# 004-H-01_SD_data_logger.net
KiCad netlist of a schematic drawn in Altium Designer
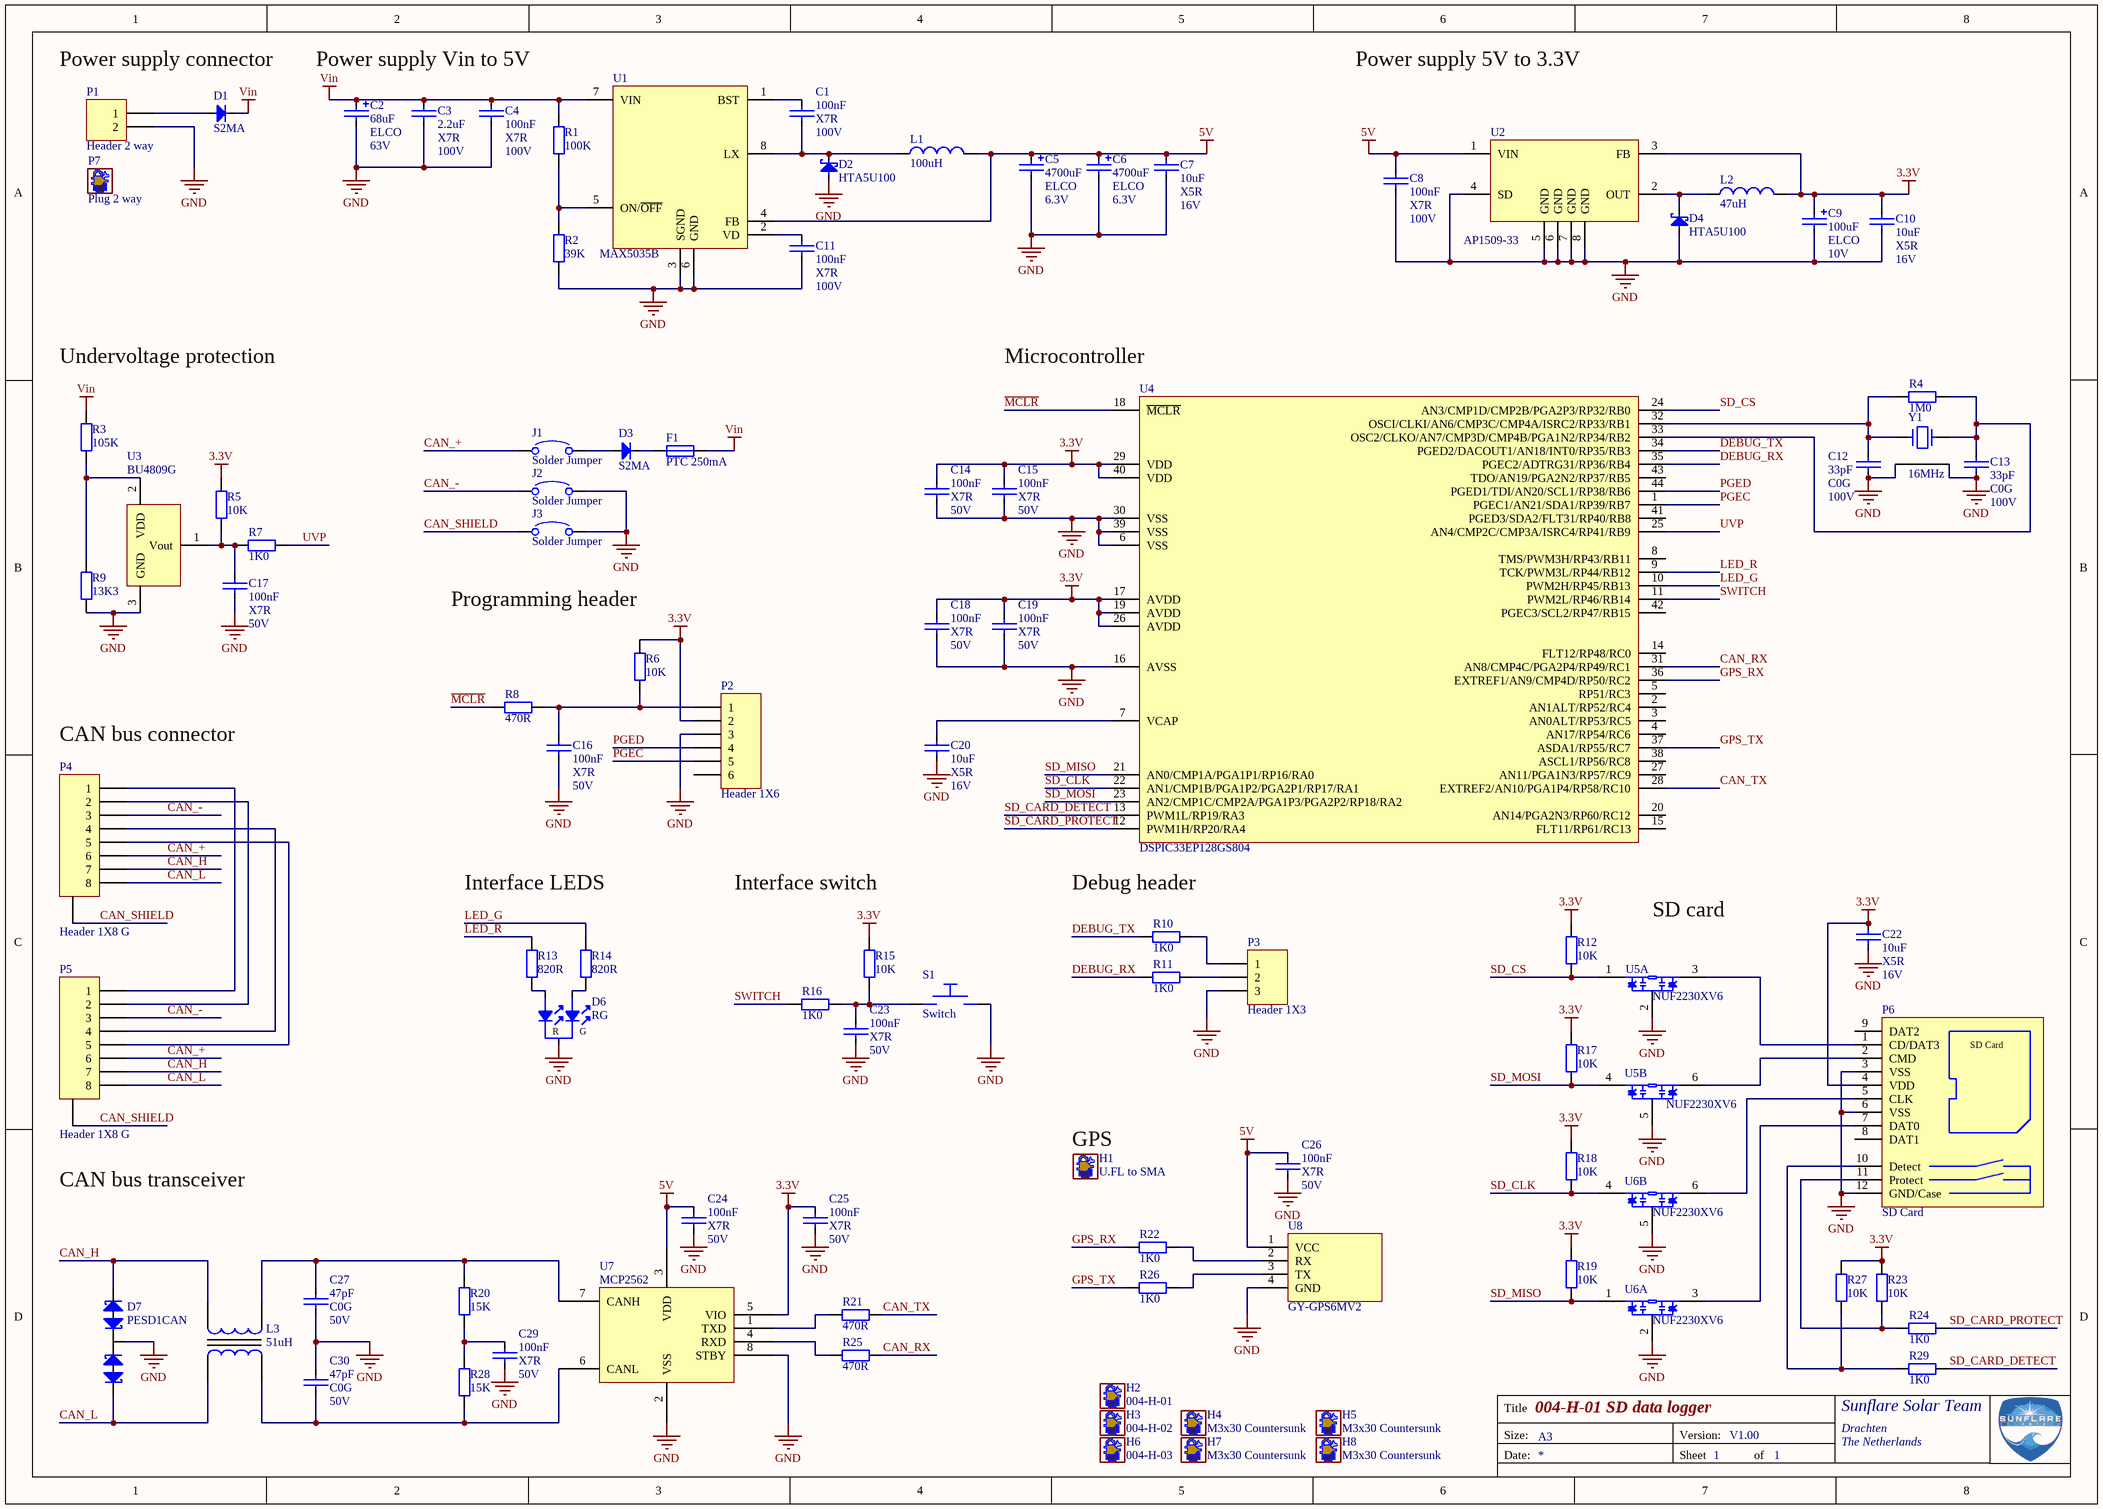
[diagram p0: 004-H-01 SD data logger.SchDoc]

(export (version "E")
  (design (tool "Eeschema 10.0.6"))
  (components
    (comp (ref "C1")
      (value "100nF")
      (footprint "CAP0805")
      (description "Capacitor")
      (fields (field (name "DIELECTRIC") "X7R") (field (name "VOLTAGERATING") "100V"))
      (libsource (lib "004-H-01 SD data logger") (part "Capacitor"))
    )
    (comp (ref "C2")
      (value "68uF")
      (footprint "CAPP8383X62N")
      (description "Capacitor Pol")
      (fields
        (field (name "MANUFACTURER") "Panasonic")
        (field (name "MANUFACTURER PART NO") "EEEFK1J680UP")
        (field (name "DIELECTRIC") "ELCO")
        (field (name "VOLTAGERATING") "63V")
      )
      (libsource (lib "004-H-01 SD data logger") (part "CapacitorPol"))
    )
    (comp (ref "C3")
      (value "2.2uF")
      (footprint "CAP1210")
      (description "Capacitor")
      (fields
        (field (name "MANUFACTURER") "AVX")
        (field (name "MANUFACTURER PART NO") "C1210X225K1RACTU")
        (field (name "DIELECTRIC") "X7R")
        (field (name "VOLTAGERATING") "100V")
      )
      (libsource (lib "004-H-01 SD data logger") (part "Capacitor"))
    )
    (comp (ref "C4")
      (value "100nF")
      (footprint "CAP0805")
      (description "Capacitor")
      (fields (field (name "DIELECTRIC") "X7R") (field (name "VOLTAGERATING") "100V"))
      (libsource (lib "004-H-01 SD data logger") (part "Capacitor"))
    )
    (comp (ref "C5")
      (value "4700uF")
      (footprint "CAPPOL_leaded_D12_5L20P5")
      (description "Capacitor Pol")
      (fields
        (field (name "MANUFACTURER") "Panasonic")
        (field (name "MANUFACTURER PART NO") "ECA0JM472")
        (field (name "DIELECTRIC") "ELCO")
        (field (name "VOLTAGERATING") "6.3V")
      )
      (libsource (lib "004-H-01 SD data logger") (part "CapacitorPol"))
    )
    (comp (ref "C6")
      (value "4700uF")
      (footprint "CAPPOL_leaded_D12_5L20P5")
      (description "Capacitor Pol")
      (fields
        (field (name "MANUFACTURER") "Panasonic")
        (field (name "MANUFACTURER PART NO") "ECA0JM472")
        (field (name "DIELECTRIC") "ELCO")
        (field (name "VOLTAGERATING") "6.3V")
      )
      (libsource (lib "004-H-01 SD data logger") (part "CapacitorPol"))
    )
    (comp (ref "C7")
      (value "10uF")
      (footprint "CAP1210")
      (description "Capacitor")
      (fields
        (field (name "MANUFACTURER") "Multicomp")
        (field (name "MANUFACTURER PART NO") "MC1210X106K160CT")
        (field (name "DIELECTRIC") "X5R")
        (field (name "VOLTAGERATING") "16V")
      )
      (libsource (lib "004-H-01 SD data logger") (part "Capacitor"))
    )
    (comp (ref "C8")
      (value "100nF")
      (footprint "CAP0805")
      (description "Capacitor")
      (fields (field (name "DIELECTRIC") "X7R") (field (name "VOLTAGERATING") "100V"))
      (libsource (lib "004-H-01 SD data logger") (part "Capacitor"))
    )
    (comp (ref "C9")
      (value "100uF")
      (footprint "CAPP8383X62N")
      (description "Capacitor Pol")
      (fields
        (field (name "MANUFACTURER") "Panasonic")
        (field (name "MANUFACTURER PART NO") "EEEHA1A101P")
        (field (name "DIELECTRIC") "ELCO")
        (field (name "VOLTAGERATING") "10V")
      )
      (libsource (lib "004-H-01 SD data logger") (part "CapacitorPol"))
    )
    (comp (ref "C10")
      (value "10uF")
      (footprint "CAP1210")
      (description "Capacitor")
      (fields
        (field (name "MANUFACTURER") "Multicomp")
        (field (name "MANUFACTURER PART NO") "MC1210X106K160CT")
        (field (name "DIELECTRIC") "X5R")
        (field (name "VOLTAGERATING") "16V")
      )
      (libsource (lib "004-H-01 SD data logger") (part "Capacitor"))
    )
    (comp (ref "C11")
      (value "100nF")
      (footprint "CAP0805")
      (description "Capacitor")
      (fields (field (name "DIELECTRIC") "X7R") (field (name "VOLTAGERATING") "100V"))
      (libsource (lib "004-H-01 SD data logger") (part "Capacitor"))
    )
    (comp (ref "C12")
      (value "33pF")
      (footprint "CAP0603")
      (description "Capacitor")
      (fields (field (name "DIELECTRIC") "C0G") (field (name "VOLTAGERATING") "100V"))
      (libsource (lib "004-H-01 SD data logger") (part "Capacitor"))
    )
    (comp (ref "C13")
      (value "33pF")
      (footprint "CAP0603")
      (description "Capacitor")
      (fields (field (name "DIELECTRIC") "C0G") (field (name "VOLTAGERATING") "100V"))
      (libsource (lib "004-H-01 SD data logger") (part "Capacitor"))
    )
    (comp (ref "C14")
      (value "100nF")
      (footprint "CAP0603")
      (description "Capacitor")
      (fields (field (name "DIELECTRIC") "X7R") (field (name "VOLTAGERATING") "50V"))
      (libsource (lib "004-H-01 SD data logger") (part "Capacitor"))
    )
    (comp (ref "C15")
      (value "100nF")
      (footprint "CAP0603")
      (description "Capacitor")
      (fields (field (name "DIELECTRIC") "X7R") (field (name "VOLTAGERATING") "50V"))
      (libsource (lib "004-H-01 SD data logger") (part "Capacitor"))
    )
    (comp (ref "C16")
      (value "100nF")
      (footprint "CAP0603")
      (description "Capacitor")
      (fields (field (name "DIELECTRIC") "X7R") (field (name "VOLTAGERATING") "50V"))
      (libsource (lib "004-H-01 SD data logger") (part "Capacitor"))
    )
    (comp (ref "C17")
      (value "100nF")
      (footprint "CAP0603")
      (description "Capacitor")
      (fields (field (name "DIELECTRIC") "X7R") (field (name "VOLTAGERATING") "50V"))
      (libsource (lib "004-H-01 SD data logger") (part "Capacitor"))
    )
    (comp (ref "C18")
      (value "100nF")
      (footprint "CAP0603")
      (description "Capacitor")
      (fields (field (name "DIELECTRIC") "X7R") (field (name "VOLTAGERATING") "50V"))
      (libsource (lib "004-H-01 SD data logger") (part "Capacitor"))
    )
    (comp (ref "C19")
      (value "100nF")
      (footprint "CAP0603")
      (description "Capacitor")
      (fields (field (name "DIELECTRIC") "X7R") (field (name "VOLTAGERATING") "50V"))
      (libsource (lib "004-H-01 SD data logger") (part "Capacitor"))
    )
    (comp (ref "C20")
      (value "10uF")
      (footprint "CAP1210")
      (description "Capacitor")
      (fields
        (field (name "MANUFACTURER") "Multicomp")
        (field (name "MANUFACTURER PART NO") "MC1210X106K160CT")
        (field (name "DIELECTRIC") "X5R")
        (field (name "VOLTAGERATING") "16V")
      )
      (libsource (lib "004-H-01 SD data logger") (part "Capacitor"))
    )
    (comp (ref "C22")
      (value "10uF")
      (footprint "CAP1210")
      (description "Capacitor")
      (fields
        (field (name "MANUFACTURER") "Multicomp")
        (field (name "MANUFACTURER PART NO") "MC1210X106K160CT")
        (field (name "DIELECTRIC") "X5R")
        (field (name "VOLTAGERATING") "16V")
      )
      (libsource (lib "004-H-01 SD data logger") (part "Capacitor"))
    )
    (comp (ref "C23")
      (value "100nF")
      (footprint "CAP0603")
      (description "Capacitor")
      (fields (field (name "DIELECTRIC") "X7R") (field (name "VOLTAGERATING") "50V"))
      (libsource (lib "004-H-01 SD data logger") (part "Capacitor"))
    )
    (comp (ref "C24")
      (value "100nF")
      (footprint "CAP0603")
      (description "Capacitor")
      (fields (field (name "DIELECTRIC") "X7R") (field (name "VOLTAGERATING") "50V"))
      (libsource (lib "004-H-01 SD data logger") (part "Capacitor"))
    )
    (comp (ref "C25")
      (value "100nF")
      (footprint "CAP0603")
      (description "Capacitor")
      (fields (field (name "DIELECTRIC") "X7R") (field (name "VOLTAGERATING") "50V"))
      (libsource (lib "004-H-01 SD data logger") (part "Capacitor"))
    )
    (comp (ref "C26")
      (value "100nF")
      (footprint "CAP0603")
      (description "Capacitor")
      (fields (field (name "DIELECTRIC") "X7R") (field (name "VOLTAGERATING") "50V"))
      (libsource (lib "004-H-01 SD data logger") (part "Capacitor"))
    )
    (comp (ref "C27")
      (value "47pF")
      (footprint "CAP0603")
      (description "Capacitor")
      (fields (field (name "DIELECTRIC") "C0G") (field (name "VOLTAGERATING") "50V"))
      (libsource (lib "004-H-01 SD data logger") (part "Capacitor"))
    )
    (comp (ref "C29")
      (value "100nF")
      (footprint "CAP0603")
      (description "Capacitor")
      (fields (field (name "DIELECTRIC") "X7R") (field (name "VOLTAGERATING") "50V"))
      (libsource (lib "004-H-01 SD data logger") (part "Capacitor"))
    )
    (comp (ref "C30")
      (value "47pF")
      (footprint "CAP0603")
      (description "Capacitor")
      (fields (field (name "DIELECTRIC") "C0G") (field (name "VOLTAGERATING") "50V"))
      (libsource (lib "004-H-01 SD data logger") (part "Capacitor"))
    )
    (comp (ref "D1")
      (value "S2MA")
      (footprint "DIODEDO-214AC")
      (description "Diode")
      (fields (field (name "MANUFACTURER") "Multicomp"))
      (libsource (lib "004-H-01 SD data logger") (part "Diode"))
    )
    (comp (ref "D2")
      (value "HTA5U100")
      (footprint "DIODEDO-214AC")
      (description "Diode Schottky")
      (fields (field (name "MANUFACTURER") "Multicomp"))
      (libsource (lib "004-H-01 SD data logger") (part "Diode Schottky"))
    )
    (comp (ref "D3")
      (value "S2MA")
      (footprint "DIODEDO-214AC")
      (description "Diode")
      (fields (field (name "MANUFACTURER") "Multicomp"))
      (libsource (lib "004-H-01 SD data logger") (part "Diode"))
    )
    (comp (ref "D4")
      (value "HTA5U100")
      (footprint "DIODEDO-214AC")
      (description "Diode Schottky")
      (fields (field (name "MANUFACTURER") "Multicomp"))
      (libsource (lib "004-H-01 SD data logger") (part "Diode Schottky"))
    )
    (comp (ref "D6")
      (value "RG")
      (footprint "LED_RG_COMMON_GND")
      (description "Led RG")
      (fields (field (name "MANUFACTURER") "Multicomp") (field (name "MANUFACTURER PART NO") "MCL039PURGW"))
      (libsource (lib "004-H-01 SD data logger") (part "Led_RG_Common_GND"))
    )
    (comp (ref "D7")
      (value "PESD1CAN")
      (footprint "SOT23-3N")
      (description "ESD Protection Device, TVS, 70 V, SOT-23, 3 Pins")
      (fields (field (name "MANUFACTURER") "NXP"))
      (libsource (lib "004-H-01 SD data logger") (part "PESD1CAN"))
    )
    (comp (ref "F1")
      (value "PTC 250mA")
      (footprint "Fuse1210")
      (description "Fuse")
      (fields (field (name "MANUFACTURER") "Bel Fuse") (field (name "MANUFACTURER PART NO") "0ZCH0010FF2E"))
      (libsource (lib "004-H-01 SD data logger") (part "Fuse"))
    )
    (comp (ref "H1")
      (value "U.FL to SMA")
      (description "RF / Coaxial Cable Assembly, U.FL Jack to SMA Bulkhead Jack, 50 ohm, 0.25 ft, 75 mm")
      (fields
        (field (name "MANUFACTURER") "RF SOLUTIONS")
        (field (name "MANUFACTURER PART NO") "CBA-UFLSMA-1")
      )
      (libsource (lib "004-H-01 SD data logger") (part "Hardware"))
    )
    (comp (ref "H2")
      (value "004-H-01")
      (description "PCB")
      (libsource (lib "004-H-01 SD data logger") (part "Hardware"))
    )
    (comp (ref "H3")
      (value "004-H-02")
      (description "Casing bottom")
      (libsource (lib "004-H-01 SD data logger") (part "Hardware"))
    )
    (comp (ref "H4")
      (value "M3x30 Countersunk")
      (description "M3x30 Xountersunk Bolt")
      (libsource (lib "004-H-01 SD data logger") (part "Hardware"))
    )
    (comp (ref "H5")
      (value "M3x30 Countersunk")
      (description "M3x30 Xountersunk Bolt")
      (libsource (lib "004-H-01 SD data logger") (part "Hardware"))
    )
    (comp (ref "H6")
      (value "004-H-03")
      (description "Casing top")
      (libsource (lib "004-H-01 SD data logger") (part "Hardware"))
    )
    (comp (ref "H7")
      (value "M3x30 Countersunk")
      (description "M3x30 Xountersunk Bolt")
      (libsource (lib "004-H-01 SD data logger") (part "Hardware"))
    )
    (comp (ref "H8")
      (value "M3x30 Countersunk")
      (description "M3x30 Xountersunk Bolt")
      (libsource (lib "004-H-01 SD data logger") (part "Hardware"))
    )
    (comp (ref "J1")
      (value "Solder Jumper")
      (footprint "SolderJumer")
      (description "Solder jumper open")
      (libsource (lib "004-H-01 SD data logger") (part "SolderJumper"))
    )
    (comp (ref "J2")
      (value "Solder Jumper")
      (footprint "SolderJumer")
      (description "Solder jumper open")
      (libsource (lib "004-H-01 SD data logger") (part "SolderJumper"))
    )
    (comp (ref "J3")
      (value "Solder Jumper")
      (footprint "SolderJumer")
      (description "Solder jumper open")
      (libsource (lib "004-H-01 SD data logger") (part "SolderJumper"))
    )
    (comp (ref "L1")
      (value "100uH")
      (footprint "INDP3030X28N")
      (description "Inductor")
      (fields (field (name "MANUFACTURER") "BOURNS") (field (name "MANUFACTURER PART NO") "SDR0302-101KL"))
      (libsource (lib "004-H-01 SD data logger") (part "Inductor"))
    )
    (comp (ref "L2")
      (value "47uH")
      (footprint "INDP3030X28N")
      (description "Inductor")
      (fields (field (name "MANUFACTURER") "Bourns") (field (name "MANUFACTURER PART NO") "SDR0302-470KL"))
      (libsource (lib "004-H-01 SD data logger") (part "Inductor"))
    )
    (comp (ref "L3")
      (value "51uH")
      (footprint "IND200P450X300-4N")
      (description "Choke common mode")
      (fields (field (name "MANUFACTURER") "Bourns") (field (name "MANUFACTURER PART NO") "SRF4532-510Y"))
      (libsource (lib "004-H-01 SD data logger") (part "Choke Common Mode"))
    )
    (comp (ref "P1")
      (value "Header 2 way")
      (footprint "21.95MH/2-E")
      (fields
        (field (name "MANUFACTURER") "IMO PRECISION CONTROLS")
        (field (name "MANUFACTURER PART NO") "21.95MH/2-E")
      )
      (libsource (lib "004-H-01 SD data logger") (part "Header1X2"))
    )
    (comp (ref "P2")
      (value "Header 1X6")
      (footprint "Header1X6P100")
      (description "Connector 1X6")
      (fields (field (name "MANUFACTURER") "Multicomp") (field (name "MANUFACTURER PART NO") "2211S-06G"))
      (libsource (lib "004-H-01 SD data logger") (part "Header1X6"))
    )
    (comp (ref "P3")
      (value "Header 1X3")
      (footprint "Header1X3P100")
      (description "Connector 1X3")
      (fields (field (name "MANUFACTURER") "Multicomp") (field (name "MANUFACTURER PART NO") "2211S-03G"))
      (libsource (lib "004-H-01 SD data logger") (part "Header1X3"))
    )
    (comp (ref "P4")
      (value "Header 1X8 G")
      (footprint "TECO-1-406541-5")
      (description "Connector 1X8 with Ground")
      (fields
        (field (name "MANUFACTURER") "TE CONNECTIVITY")
        (field (name "MANUFACTURER PART NO") "1-406541-5")
      )
      (libsource (lib "004-H-01 SD data logger") (part "Header1X8+G"))
    )
    (comp (ref "P5")
      (value "Header 1X8 G")
      (footprint "TECO-1-406541-5")
      (description "Connector 1X8 with Ground")
      (fields
        (field (name "MANUFACTURER") "TE CONNECTIVITY")
        (field (name "MANUFACTURER PART NO") "1-406541-5")
      )
      (libsource (lib "004-H-01 SD data logger") (part "Header1X8+G"))
    )
    (comp (ref "P6")
      (value "SD Card")
      (footprint "SDK-9BNS-K13-GS-TB")
      (description "SD slot connector with card detect and protect")
      (fields (field (name "MANUFACTURER") "JST") (field (name "MANUFACTURER PART NO") "SDK-9BNS-K13-GS-TB"))
      (libsource (lib "004-H-01 SD data logger") (part "SD slot"))
    )
    (comp (ref "P7")
      (value "Plug 2 way")
      (description "Generaric hardware")
      (fields
        (field (name "MANUFACTURER") "IMO PRECISION CONTROLS")
        (field (name "MANUFACTURER PART NO") "21.950M/2-E")
      )
      (libsource (lib "004-H-01 SD data logger") (part "Hardware"))
    )
    (comp (ref "R1")
      (value "100K")
      (footprint "RES0805")
      (description "Resistor")
      (fields (field (name "TOLERANCE") "1%"))
      (libsource (lib "") (part "Resistor_1"))
    )
    (comp (ref "R2")
      (value "39K")
      (footprint "RES0805")
      (description "Resistor")
      (fields (field (name "TOLERANCE") "1%"))
      (libsource (lib "") (part "Resistor_1"))
    )
    (comp (ref "R3")
      (value "105K")
      (footprint "RES0805")
      (description "Resistor")
      (fields (field (name "TOLERANCE") "1%"))
      (libsource (lib "") (part "Resistor_1"))
    )
    (comp (ref "R4")
      (value "1M0")
      (footprint "RES0603")
      (description "Resistor")
      (fields (field (name "TOLERANCE") "1%"))
      (libsource (lib "004-H-01 SD data logger") (part "Resistor"))
    )
    (comp (ref "R5")
      (value "10K")
      (footprint "RES0603")
      (description "Resistor")
      (fields (field (name "TOLERANCE") "1%"))
      (libsource (lib "") (part "Resistor_1"))
    )
    (comp (ref "R6")
      (value "10K")
      (footprint "RES0603")
      (description "Resistor")
      (fields (field (name "TOLERANCE") "1%"))
      (libsource (lib "") (part "Resistor_1"))
    )
    (comp (ref "R7")
      (value "1K0")
      (footprint "RES0603")
      (description "Resistor")
      (fields (field (name "TOLERANCE") "1%"))
      (libsource (lib "004-H-01 SD data logger") (part "Resistor"))
    )
    (comp (ref "R8")
      (value "470R")
      (footprint "RES0603")
      (description "Resistor")
      (fields (field (name "TOLERANCE") "1%"))
      (libsource (lib "004-H-01 SD data logger") (part "Resistor"))
    )
    (comp (ref "R9")
      (value "13K3")
      (footprint "RES0805")
      (description "Resistor")
      (fields (field (name "TOLERANCE") "1%"))
      (libsource (lib "") (part "Resistor_1"))
    )
    (comp (ref "R10")
      (value "1K0")
      (footprint "RES0603")
      (description "Resistor")
      (fields (field (name "TOLERANCE") "1%"))
      (libsource (lib "004-H-01 SD data logger") (part "Resistor"))
    )
    (comp (ref "R11")
      (value "1K0")
      (footprint "RES0603")
      (description "Resistor")
      (fields (field (name "TOLERANCE") "1%"))
      (libsource (lib "004-H-01 SD data logger") (part "Resistor"))
    )
    (comp (ref "R12")
      (value "10K")
      (footprint "RES0603")
      (description "Resistor")
      (fields (field (name "TOLERANCE") "1%"))
      (libsource (lib "") (part "Resistor_1"))
    )
    (comp (ref "R13")
      (value "820R")
      (footprint "RES0603")
      (description "Resistor")
      (fields (field (name "TOLERANCE") "1%"))
      (libsource (lib "") (part "Resistor_1"))
    )
    (comp (ref "R14")
      (value "820R")
      (footprint "RES0603")
      (description "Resistor")
      (fields (field (name "TOLERANCE") "1%"))
      (libsource (lib "") (part "Resistor_1"))
    )
    (comp (ref "R15")
      (value "10K")
      (footprint "RES0603")
      (description "Resistor")
      (fields (field (name "TOLERANCE") "1%"))
      (libsource (lib "") (part "Resistor_1"))
    )
    (comp (ref "R16")
      (value "1K0")
      (footprint "RES0603")
      (description "Resistor")
      (fields (field (name "TOLERANCE") "1%"))
      (libsource (lib "004-H-01 SD data logger") (part "Resistor"))
    )
    (comp (ref "R17")
      (value "10K")
      (footprint "RES0603")
      (description "Resistor")
      (fields (field (name "TOLERANCE") "1%"))
      (libsource (lib "") (part "Resistor_1"))
    )
    (comp (ref "R18")
      (value "10K")
      (footprint "RES0603")
      (description "Resistor")
      (fields (field (name "TOLERANCE") "1%"))
      (libsource (lib "") (part "Resistor_1"))
    )
    (comp (ref "R19")
      (value "10K")
      (footprint "RES0603")
      (description "Resistor")
      (fields (field (name "TOLERANCE") "1%"))
      (libsource (lib "") (part "Resistor_1"))
    )
    (comp (ref "R20")
      (value "15K")
      (footprint "RES0603")
      (description "Resistor")
      (fields (field (name "TOLERANCE") "1%"))
      (libsource (lib "") (part "Resistor_1"))
    )
    (comp (ref "R21")
      (value "470R")
      (footprint "RES0603")
      (description "Resistor")
      (fields (field (name "TOLERANCE") "1%"))
      (libsource (lib "004-H-01 SD data logger") (part "Resistor"))
    )
    (comp (ref "R22")
      (value "1K0")
      (footprint "RES0603")
      (description "Resistor")
      (fields (field (name "TOLERANCE") "1%"))
      (libsource (lib "004-H-01 SD data logger") (part "Resistor"))
    )
    (comp (ref "R23")
      (value "10K")
      (footprint "RES0603")
      (description "Resistor")
      (fields (field (name "TOLERANCE") "1%"))
      (libsource (lib "") (part "Resistor_1"))
    )
    (comp (ref "R24")
      (value "1K0")
      (footprint "RES0603")
      (description "Resistor")
      (fields (field (name "TOLERANCE") "1%"))
      (libsource (lib "004-H-01 SD data logger") (part "Resistor"))
    )
    (comp (ref "R25")
      (value "470R")
      (footprint "RES0603")
      (description "Resistor")
      (fields (field (name "TOLERANCE") "1%"))
      (libsource (lib "004-H-01 SD data logger") (part "Resistor"))
    )
    (comp (ref "R26")
      (value "1K0")
      (footprint "RES0603")
      (description "Resistor")
      (fields (field (name "TOLERANCE") "1%"))
      (libsource (lib "004-H-01 SD data logger") (part "Resistor"))
    )
    (comp (ref "R27")
      (value "10K")
      (footprint "RES0603")
      (description "Resistor")
      (fields (field (name "TOLERANCE") "1%"))
      (libsource (lib "") (part "Resistor_1"))
    )
    (comp (ref "R28")
      (value "15K")
      (footprint "RES0603")
      (description "Resistor")
      (fields (field (name "TOLERANCE") "1%"))
      (libsource (lib "") (part "Resistor_1"))
    )
    (comp (ref "R29")
      (value "1K0")
      (footprint "RES0603")
      (description "Resistor")
      (fields (field (name "TOLERANCE") "1%"))
      (libsource (lib "004-H-01 SD data logger") (part "Resistor"))
    )
    (comp (ref "S1")
      (value "Switch")
      (footprint "FSMRA4JH")
      (description "Tactile Switch")
      (fields
        (field (name "MANUFACTURER") "TE CONNECTIVITY")
        (field (name "MANUFACTURER PART NO") "FSMRA4JH")
      )
      (libsource (lib "004-H-01 SD data logger") (part "TactileSwitch"))
    )
    (comp (ref "U1")
      (value "MAX5035B")
      (footprint "SOIC-8N")
      (description "5V 1A, 76V, High-Efficiency MAXPower Step-Down DC-DC Converter")
      (fields
        (field (name "MANUFACTURER") "Maxim Integrated Products")
        (field (name "MANUFACTURER PART NO") "MAX5035BUSA+T")
      )
      (libsource (lib "004-H-01 SD data logger") (part "MAX5035B"))
    )
    (comp (ref "U2")
      (value "AP1509-33")
      (footprint "SOIC-8N")
      (description "150KHz, 2A PWM BUCK DC/DC CONVERTER")
      (fields
        (field (name "MANUFACTURER") "Diodes Inc")
        (field (name "MANUFACTURER PART NO") "AP1509-33SG-13")
      )
      (libsource (lib "004-H-01 SD data logger") (part "AP1509-33"))
    )
    (comp (ref "U3")
      (value "BU4809G")
      (footprint "SOT95P280X125-5N")
      (description "Voltage Detector")
      (fields (field (name "MANUFACTURER") "ROHM") (field (name "MANUFACTURER PART NO") "BU4809G-TR"))
      (libsource (lib "004-H-01 SD data logger") (part "BD48xx"))
    )
    (comp (ref "U4")
      (value "DSPIC33EP128GS804")
      (footprint "TQFP80P1200X1200X120-44N")
      (fields
        (field (name "MANUFACTURER") "Microchip")
        (field (name "MANUFACTURER PART NO") "DSPIC33EP128GS804-I/PT")
      )
      (libsource (lib "004-H-01 SD data logger") (part "DSPIC33EP128GS804"))
    )
    (comp (ref "U5")
      (value "NUF2230XV6")
      (footprint "SOT50P160X60-6N")
      (description "2 Line EMI Filter with ESDProtection")
      (fields
        (field (name "MANUFACTURER") "ON SEMICONDUCTOR")
        (field (name "MANUFACTURER PART NO") "NUF2230XV6T1G")
      )
      (libsource (lib "004-H-01 SD data logger") (part "NUF2230XV6"))
    )
    (comp (ref "U6")
      (value "NUF2230XV6")
      (footprint "SOT50P160X60-6N")
      (description "2 Line EMI Filter with ESDProtection")
      (fields
        (field (name "MANUFACTURER") "ON SEMICONDUCTOR")
        (field (name "MANUFACTURER PART NO") "NUF2230XV6T1G")
      )
      (libsource (lib "004-H-01 SD data logger") (part "NUF2230XV6"))
    )
    (comp (ref "U7")
      (value "MCP2562")
      (footprint "SOIC-8N")
      (description "CAN Bus, Transceiver, CAN, LIN, 1, 1, 4.5 V, 5.5 V, SOIC")
      (fields (field (name "MANUFACTURER") "Microchip") (field (name "MANUFACTURER PART NO") "MCP2562-E/SN"))
      (libsource (lib "004-H-01 SD data logger") (part "MCP2562"))
    )
    (comp (ref "U8")
      (value "GY-GPS6MV2")
      (footprint "GY-GPS6MV2")
      (description "GPS module")
      (fields (field (name "MANUFACTURER") "Ebay") (field (name "MANUFACTURER PART NO") "GY-NEO6MV2"))
      (libsource (lib "004-H-01 SD data logger") (part "GY-GPS6MV2"))
    )
    (comp (ref "Y1")
      (value "16MHz")
      (footprint "CrystalSMD 5032")
      (description "Crystal")
      (fields
        (field (name "MANUFACTURER") "MULTICOMP")
        (field (name "MANUFACTURER PART NO") "MCSJK-7I-16.00-18-30-60-B-30")
      )
      (libsource (lib "004-H-01 SD data logger") (part "Crystal_1"))
    )
  )
  (nets
    (net (code "1") (name "/CAN_+") (class "Default")
      (node (ref "J1") (pin "1") (pinfunction "1_1") (pintype "passive"))
      (node (ref "P4") (pin "6") (pinfunction "6_6") (pintype "passive"))
      (node (ref "P5") (pin "6") (pinfunction "6_6") (pintype "passive"))
    )
    (net (code "2") (name "/CAN_-") (class "Default")
      (node (ref "J2") (pin "1") (pinfunction "1_1") (pintype "passive"))
      (node (ref "P4") (pin "3") (pinfunction "3_3") (pintype "passive"))
      (node (ref "P5") (pin "3") (pinfunction "3_3") (pintype "passive"))
    )
    (net (code "3") (name "/CAN_H") (class "Default")
      (node (ref "D7") (pin "1") (pinfunction "1_1") (pintype "passive"))
      (node (ref "L3") (pin "4") (pinfunction "4_4") (pintype "passive"))
      (node (ref "P4") (pin "7") (pinfunction "7_7") (pintype "passive"))
      (node (ref "P5") (pin "7") (pinfunction "7_7") (pintype "passive"))
    )
    (net (code "4") (name "/CAN_L") (class "Default")
      (node (ref "D7") (pin "2") (pinfunction "2_2") (pintype "passive"))
      (node (ref "L3") (pin "1") (pinfunction "1_1") (pintype "passive"))
      (node (ref "P4") (pin "8") (pinfunction "8_8") (pintype "passive"))
      (node (ref "P5") (pin "8") (pinfunction "8_8") (pintype "passive"))
    )
    (net (code "5") (name "/CAN_RX") (class "Default")
      (node (ref "R25") (pin "2") (pinfunction "2_2") (pintype "passive"))
      (node (ref "U4") (pin "31") (pinfunction "AN8/CMP4C/PGA2P4/RP49/RC1_31") (pintype "passive"))
    )
    (net (code "6") (name "/CAN_SHIELD") (class "Default")
      (node (ref "J3") (pin "1") (pinfunction "1_1") (pintype "passive"))
      (node (ref "P4") (pin "9") (pinfunction "G_9") (pintype "passive"))
      (node (ref "P5") (pin "9") (pinfunction "G_9") (pintype "passive"))
    )
    (net (code "7") (name "/CAN_TX") (class "Default")
      (node (ref "R21") (pin "2") (pinfunction "2_2") (pintype "passive"))
      (node (ref "U4") (pin "28") (pinfunction "EXTREF2/AN10/PGA1P4/RP58/RC10_28") (pintype "passive"))
    )
    (net (code "8") (name "/DEBUG_RX") (class "Default")
      (node (ref "R11") (pin "1") (pinfunction "1_1") (pintype "passive"))
      (node (ref "U4") (pin "35") (pinfunction "PGEC2/ADTRG31/RP36/RB4_35") (pintype "passive"))
    )
    (net (code "9") (name "/DEBUG_TX") (class "Default")
      (node (ref "R10") (pin "1") (pinfunction "1_1") (pintype "passive"))
      (node (ref "U4") (pin "34") (pinfunction "PGED2/DACOUT1/AN18/INT0/RP35/RB3_34") (pintype "passive"))
    )
    (net (code "10") (name "/GPS_RX") (class "Default")
      (node (ref "R22") (pin "1") (pinfunction "1_1") (pintype "passive"))
      (node (ref "U4") (pin "36") (pinfunction "EXTREF1/AN9/CMP4D/RP50/RC2_36") (pintype "passive"))
    )
    (net (code "11") (name "/GPS_TX") (class "Default")
      (node (ref "R26") (pin "1") (pinfunction "1_1") (pintype "passive"))
      (node (ref "U4") (pin "37") (pinfunction "ASDA1/RP55/RC7_37") (pintype "passive"))
    )
    (net (code "12") (name "/LED_G") (class "Default")
      (node (ref "R14") (pin "1") (pinfunction "1_1") (pintype "passive"))
      (node (ref "U4") (pin "10") (pinfunction "PWM2H/RP45/RB13_10") (pintype "passive"))
    )
    (net (code "13") (name "/LED_R") (class "Default")
      (node (ref "R13") (pin "1") (pinfunction "1_1") (pintype "passive"))
      (node (ref "U4") (pin "9") (pinfunction "TCK/PWM3L/RP44/RB12_9") (pintype "passive"))
    )
    (net (code "14") (name "/PGEC") (class "Default")
      (node (ref "P2") (pin "5") (pinfunction "5_5") (pintype "passive"))
      (node (ref "U4") (pin "1") (pinfunction "PGEC1/AN21/SDA1/RP39/RB7_1") (pintype "passive"))
    )
    (net (code "15") (name "/PGED") (class "Default")
      (node (ref "P2") (pin "4") (pinfunction "4_4") (pintype "passive"))
      (node (ref "U4") (pin "44") (pinfunction "PGED1/TDI/AN20/SCL1/RP38/RB6_44") (pintype "passive"))
    )
    (net (code "16") (name "/SD_CARD_DETECT") (class "Default")
      (node (ref "R29") (pin "2") (pinfunction "2_2") (pintype "passive"))
      (node (ref "U4") (pin "13") (pinfunction "PWM1L/RP19/RA3_13") (pintype "passive"))
    )
    (net (code "17") (name "/SD_CARD_PROTECT") (class "Default")
      (node (ref "R24") (pin "2") (pinfunction "2_2") (pintype "passive"))
      (node (ref "U4") (pin "12") (pinfunction "PWM1H/RP20/RA4_12") (pintype "passive"))
    )
    (net (code "18") (name "/SD_CLK") (class "Default")
      (node (ref "R18") (pin "2") (pinfunction "2_2") (pintype "passive"))
      (node (ref "U4") (pin "22") (pinfunction "AN1/CMP1B/PGA1P2/PGA2P1/RP17/RA1_22") (pintype "passive"))
      (node (ref "U6") (pin "4") (pinfunction "4_4") (pintype "passive"))
    )
    (net (code "19") (name "/SD_CS") (class "Default")
      (node (ref "R12") (pin "2") (pinfunction "2_2") (pintype "passive"))
      (node (ref "U4") (pin "24") (pinfunction "AN3/CMP1D/CMP2B/PGA2P3/RP32/RB0_24") (pintype "passive"))
      (node (ref "U5") (pin "1") (pinfunction "1_1") (pintype "passive"))
    )
    (net (code "20") (name "/SD_MISO") (class "Default")
      (node (ref "R19") (pin "2") (pinfunction "2_2") (pintype "passive"))
      (node (ref "U4") (pin "21") (pinfunction "AN0/CMP1A/PGA1P1/RP16/RA0_21") (pintype "passive"))
      (node (ref "U6") (pin "1") (pinfunction "1_1") (pintype "passive"))
    )
    (net (code "21") (name "/SD_MOSI") (class "Default")
      (node (ref "R17") (pin "2") (pinfunction "2_2") (pintype "passive"))
      (node (ref "U4") (pin "23") (pinfunction "AN2/CMP1C/CMP2A/PGA1P3/PGA2P2/RP18/RA2_23") (pintype "passive"))
      (node (ref "U5") (pin "4") (pinfunction "4_4") (pintype "passive"))
    )
    (net (code "22") (name "/SWITCH") (class "Default")
      (node (ref "R16") (pin "1") (pinfunction "1_1") (pintype "passive"))
      (node (ref "U4") (pin "11") (pinfunction "PWM2L/RP46/RB14_11") (pintype "passive"))
    )
    (net (code "23") (name "/UVP") (class "Default")
      (node (ref "R7") (pin "2") (pinfunction "2_2") (pintype "passive"))
      (node (ref "U4") (pin "25") (pinfunction "AN4/CMP2C/CMP3A/ISRC4/RP41/RB9_25") (pintype "passive"))
    )
    (net (code "24") (name "/~{MCLR}") (class "Default")
      (node (ref "R8") (pin "1") (pinfunction "1_1") (pintype "passive"))
      (node (ref "U4") (pin "18") (pinfunction "~{MCLR}_18") (pintype "passive"))
    )
    (net (code "25") (name "3.3V") (class "Default")
      (node (ref "C10") (pin "2") (pinfunction "2_2") (pintype "passive"))
      (node (ref "C14") (pin "2") (pinfunction "2_2") (pintype "passive"))
      (node (ref "C15") (pin "2") (pinfunction "2_2") (pintype "passive"))
      (node (ref "C18") (pin "2") (pinfunction "2_2") (pintype "passive"))
      (node (ref "C19") (pin "2") (pinfunction "2_2") (pintype "passive"))
      (node (ref "C22") (pin "2") (pinfunction "2_2") (pintype "passive"))
      (node (ref "C25") (pin "2") (pinfunction "2_2") (pintype "passive"))
      (node (ref "C9") (pin "1") (pinfunction "1_1") (pintype "passive"))
      (node (ref "L2") (pin "2") (pinfunction "2_2") (pintype "passive"))
      (node (ref "P2") (pin "2") (pinfunction "2_2") (pintype "passive"))
      (node (ref "P6") (pin "4") (pinfunction "VDD_4") (pintype "passive"))
      (node (ref "R12") (pin "1") (pinfunction "1_1") (pintype "passive"))
      (node (ref "R15") (pin "1") (pinfunction "1_1") (pintype "passive"))
      (node (ref "R17") (pin "1") (pinfunction "1_1") (pintype "passive"))
      (node (ref "R18") (pin "1") (pinfunction "1_1") (pintype "passive"))
      (node (ref "R19") (pin "1") (pinfunction "1_1") (pintype "passive"))
      (node (ref "R23") (pin "1") (pinfunction "1_1") (pintype "passive"))
      (node (ref "R27") (pin "1") (pinfunction "1_1") (pintype "passive"))
      (node (ref "R5") (pin "1") (pinfunction "1_1") (pintype "passive"))
      (node (ref "R6") (pin "1") (pinfunction "1_1") (pintype "passive"))
      (node (ref "U2") (pin "3") (pinfunction "FB_3") (pintype "passive"))
      (node (ref "U4") (pin "17") (pinfunction "AVDD_17") (pintype "passive"))
      (node (ref "U4") (pin "19") (pinfunction "AVDD_19") (pintype "passive"))
      (node (ref "U4") (pin "26") (pinfunction "AVDD_26") (pintype "passive"))
      (node (ref "U4") (pin "29") (pinfunction "VDD_29") (pintype "passive"))
      (node (ref "U4") (pin "40") (pinfunction "VDD_40") (pintype "passive"))
      (node (ref "U7") (pin "5") (pinfunction "VIO_5") (pintype "passive"))
    )
    (net (code "26") (name "5V") (class "Default")
      (node (ref "C24") (pin "2") (pinfunction "2_2") (pintype "passive"))
      (node (ref "C26") (pin "2") (pinfunction "2_2") (pintype "passive"))
      (node (ref "C5") (pin "1") (pinfunction "1_1") (pintype "passive"))
      (node (ref "C6") (pin "1") (pinfunction "1_1") (pintype "passive"))
      (node (ref "C7") (pin "2") (pinfunction "2_2") (pintype "passive"))
      (node (ref "C8") (pin "2") (pinfunction "2_2") (pintype "passive"))
      (node (ref "L1") (pin "2") (pinfunction "2_2") (pintype "passive"))
      (node (ref "U1") (pin "4") (pinfunction "FB_4") (pintype "passive"))
      (node (ref "U2") (pin "1") (pinfunction "VIN_1") (pintype "passive"))
      (node (ref "U7") (pin "3") (pinfunction "VDD_3") (pintype "passive"))
      (node (ref "U8") (pin "1") (pinfunction "VCC_1") (pintype "passive"))
    )
    (net (code "27") (name "GND") (class "Default")
      (node (ref "C10") (pin "1") (pinfunction "1_1") (pintype "passive"))
      (node (ref "C11") (pin "1") (pinfunction "1_1") (pintype "passive"))
      (node (ref "C12") (pin "1") (pinfunction "1_1") (pintype "passive"))
      (node (ref "C13") (pin "1") (pinfunction "1_1") (pintype "passive"))
      (node (ref "C14") (pin "1") (pinfunction "1_1") (pintype "passive"))
      (node (ref "C15") (pin "1") (pinfunction "1_1") (pintype "passive"))
      (node (ref "C16") (pin "2") (pinfunction "2_2") (pintype "passive"))
      (node (ref "C17") (pin "2") (pinfunction "2_2") (pintype "passive"))
      (node (ref "C18") (pin "1") (pinfunction "1_1") (pintype "passive"))
      (node (ref "C19") (pin "1") (pinfunction "1_1") (pintype "passive"))
      (node (ref "C2") (pin "2") (pinfunction "2_2") (pintype "passive"))
      (node (ref "C20") (pin "1") (pinfunction "1_1") (pintype "passive"))
      (node (ref "C22") (pin "1") (pinfunction "1_1") (pintype "passive"))
      (node (ref "C23") (pin "1") (pinfunction "1_1") (pintype "passive"))
      (node (ref "C24") (pin "1") (pinfunction "1_1") (pintype "passive"))
      (node (ref "C25") (pin "1") (pinfunction "1_1") (pintype "passive"))
      (node (ref "C26") (pin "1") (pinfunction "1_1") (pintype "passive"))
      (node (ref "C27") (pin "1") (pinfunction "1_1") (pintype "passive"))
      (node (ref "C29") (pin "1") (pinfunction "1_1") (pintype "passive"))
      (node (ref "C3") (pin "1") (pinfunction "1_1") (pintype "passive"))
      (node (ref "C30") (pin "2") (pinfunction "2_2") (pintype "passive"))
      (node (ref "C4") (pin "1") (pinfunction "1_1") (pintype "passive"))
      (node (ref "C5") (pin "2") (pinfunction "2_2") (pintype "passive"))
      (node (ref "C6") (pin "2") (pinfunction "2_2") (pintype "passive"))
      (node (ref "C7") (pin "1") (pinfunction "1_1") (pintype "passive"))
      (node (ref "C8") (pin "1") (pinfunction "1_1") (pintype "passive"))
      (node (ref "C9") (pin "2") (pinfunction "2_2") (pintype "passive"))
      (node (ref "D2") (pin "2") (pinfunction "A_2") (pintype "passive"))
      (node (ref "D4") (pin "2") (pinfunction "A_2") (pintype "passive"))
      (node (ref "D6") (pin "2") (pinfunction "K_2") (pintype "passive"))
      (node (ref "D7") (pin "3") (pinfunction "3_3") (pintype "passive"))
      (node (ref "J2") (pin "2") (pinfunction "2_2") (pintype "passive"))
      (node (ref "J3") (pin "2") (pinfunction "2_2") (pintype "passive"))
      (node (ref "P1") (pin "2") (pinfunction "2_2") (pintype "passive"))
      (node (ref "P2") (pin "3") (pinfunction "3_3") (pintype "passive"))
      (node (ref "P3") (pin "3") (pinfunction "3_3") (pintype "passive"))
      (node (ref "P6") (pin "12") (pinfunction "GND/Case_12") (pintype "passive"))
      (node (ref "P6") (pin "3") (pinfunction "VSS_3") (pintype "passive"))
      (node (ref "P6") (pin "6") (pinfunction "VSS_6") (pintype "passive"))
      (node (ref "R2") (pin "2") (pinfunction "2_2") (pintype "passive"))
      (node (ref "R9") (pin "2") (pinfunction "2_2") (pintype "passive"))
      (node (ref "S1") (pin "2") (pinfunction "2_2") (pintype "passive"))
      (node (ref "U1") (pin "3") (pinfunction "SGND_3") (pintype "passive"))
      (node (ref "U1") (pin "6") (pinfunction "GND_6") (pintype "passive"))
      (node (ref "U2") (pin "4") (pinfunction "SD_4") (pintype "passive"))
      (node (ref "U2") (pin "5") (pinfunction "GND_5") (pintype "passive"))
      (node (ref "U2") (pin "6") (pinfunction "GND_6") (pintype "passive"))
      (node (ref "U2") (pin "7") (pinfunction "GND_7") (pintype "passive"))
      (node (ref "U2") (pin "8") (pinfunction "GND_8") (pintype "passive"))
      (node (ref "U3") (pin "3") (pinfunction "GND_3") (pintype "passive"))
      (node (ref "U4") (pin "16") (pinfunction "AVSS_16") (pintype "passive"))
      (node (ref "U4") (pin "30") (pinfunction "VSS_30") (pintype "passive"))
      (node (ref "U4") (pin "39") (pinfunction "VSS_39") (pintype "passive"))
      (node (ref "U4") (pin "6") (pinfunction "VSS_6") (pintype "passive"))
      (node (ref "U5") (pin "2") (pinfunction "2_2") (pintype "passive"))
      (node (ref "U5") (pin "5") (pinfunction "5_5") (pintype "passive"))
      (node (ref "U6") (pin "2") (pinfunction "2_2") (pintype "passive"))
      (node (ref "U6") (pin "5") (pinfunction "5_5") (pintype "passive"))
      (node (ref "U7") (pin "2") (pinfunction "VSS_2") (pintype "passive"))
      (node (ref "U7") (pin "8") (pinfunction "STBY_8") (pintype "passive"))
      (node (ref "U8") (pin "4") (pinfunction "GND_4") (pintype "passive"))
      (node (ref "Y1") (pin "2") (pinfunction "2_2") (pintype "passive"))
      (node (ref "Y1") (pin "4") (pinfunction "4_4") (pintype "passive"))
    )
    (net (code "28") (name "Net-(C16-Pad1)") (class "Default")
      (node (ref "C16") (pin "1") (pinfunction "1_1") (pintype "passive"))
      (node (ref "P2") (pin "1") (pinfunction "1_1") (pintype "passive"))
      (node (ref "R6") (pin "2") (pinfunction "2_2") (pintype "passive"))
      (node (ref "R8") (pin "2") (pinfunction "2_2") (pintype "passive"))
    )
    (net (code "29") (name "Net-(C23-Pad2)") (class "Default")
      (node (ref "C23") (pin "2") (pinfunction "2_2") (pintype "passive"))
      (node (ref "R15") (pin "2") (pinfunction "2_2") (pintype "passive"))
      (node (ref "R16") (pin "2") (pinfunction "2_2") (pintype "passive"))
      (node (ref "S1") (pin "1") (pinfunction "1_1") (pintype "passive"))
    )
    (net (code "30") (name "Net-(C29-Pad2)") (class "Default")
      (node (ref "C29") (pin "2") (pinfunction "2_2") (pintype "passive"))
      (node (ref "R20") (pin "2") (pinfunction "2_2") (pintype "passive"))
      (node (ref "R28") (pin "1") (pinfunction "1_1") (pintype "passive"))
    )
    (net (code "31") (name "Net-(D1-A)") (class "Default")
      (node (ref "D1") (pin "2") (pinfunction "A_2") (pintype "passive"))
      (node (ref "P1") (pin "1") (pinfunction "1_1") (pintype "passive"))
    )
    (net (code "32") (name "Net-(D2-K)") (class "Default")
      (node (ref "C1") (pin "1") (pinfunction "1_1") (pintype "passive"))
      (node (ref "D2") (pin "1") (pinfunction "K_1") (pintype "passive"))
      (node (ref "L1") (pin "1") (pinfunction "1_1") (pintype "passive"))
      (node (ref "U1") (pin "8") (pinfunction "LX_8") (pintype "passive"))
    )
    (net (code "33") (name "Net-(D3-A)") (class "Default")
      (node (ref "D3") (pin "2") (pinfunction "A_2") (pintype "passive"))
      (node (ref "J1") (pin "2") (pinfunction "2_2") (pintype "passive"))
    )
    (net (code "34") (name "Net-(D3-K)") (class "Default")
      (node (ref "D3") (pin "1") (pinfunction "K_1") (pintype "passive"))
      (node (ref "F1") (pin "1") (pinfunction "1_1") (pintype "passive"))
    )
    (net (code "35") (name "Net-(D4-K)") (class "Default")
      (node (ref "D4") (pin "1") (pinfunction "K_1") (pintype "passive"))
      (node (ref "L2") (pin "1") (pinfunction "1_1") (pintype "passive"))
      (node (ref "U2") (pin "2") (pinfunction "OUT_2") (pintype "passive"))
    )
    (net (code "36") (name "Net-(D6-A_G)") (class "Default")
      (node (ref "D6") (pin "3") (pinfunction "A_G_3") (pintype "passive"))
      (node (ref "R14") (pin "2") (pinfunction "2_2") (pintype "passive"))
    )
    (net (code "37") (name "Net-(D6-A_R)") (class "Default")
      (node (ref "D6") (pin "1") (pinfunction "A_R_1") (pintype "passive"))
      (node (ref "R13") (pin "2") (pinfunction "2_2") (pintype "passive"))
    )
    (net (code "38") (name "Net-(P3-Pad1)") (class "Default")
      (node (ref "P3") (pin "1") (pinfunction "1_1") (pintype "passive"))
      (node (ref "R10") (pin "2") (pinfunction "2_2") (pintype "passive"))
    )
    (net (code "39") (name "Net-(P3-Pad2)") (class "Default")
      (node (ref "P3") (pin "2") (pinfunction "2_2") (pintype "passive"))
      (node (ref "R11") (pin "2") (pinfunction "2_2") (pintype "passive"))
    )
    (net (code "40") (name "Net-(P4-Pad1)") (class "Default")
      (node (ref "P4") (pin "1") (pinfunction "1_1") (pintype "passive"))
      (node (ref "P5") (pin "1") (pinfunction "1_1") (pintype "passive"))
    )
    (net (code "41") (name "Net-(P4-Pad2)") (class "Default")
      (node (ref "P4") (pin "2") (pinfunction "2_2") (pintype "passive"))
      (node (ref "P5") (pin "2") (pinfunction "2_2") (pintype "passive"))
    )
    (net (code "42") (name "Net-(P4-Pad4)") (class "Default")
      (node (ref "P4") (pin "4") (pinfunction "4_4") (pintype "passive"))
      (node (ref "P5") (pin "4") (pinfunction "4_4") (pintype "passive"))
    )
    (net (code "43") (name "Net-(P4-Pad5)") (class "Default")
      (node (ref "P4") (pin "5") (pinfunction "5_5") (pintype "passive"))
      (node (ref "P5") (pin "5") (pinfunction "5_5") (pintype "passive"))
    )
    (net (code "44") (name "Net-(P6-CD{slash}DAT3)") (class "Default")
      (node (ref "P6") (pin "1") (pinfunction "CD/DAT3_1") (pintype "passive"))
      (node (ref "U5") (pin "3") (pinfunction "3_3") (pintype "passive"))
    )
    (net (code "45") (name "Net-(P6-CLK)") (class "Default")
      (node (ref "P6") (pin "5") (pinfunction "CLK_5") (pintype "passive"))
      (node (ref "U6") (pin "6") (pinfunction "6_6") (pintype "passive"))
    )
    (net (code "46") (name "Net-(P6-CMD)") (class "Default")
      (node (ref "P6") (pin "2") (pinfunction "CMD_2") (pintype "passive"))
      (node (ref "U5") (pin "6") (pinfunction "6_6") (pintype "passive"))
    )
    (net (code "47") (name "Net-(P6-DAT0)") (class "Default")
      (node (ref "P6") (pin "7") (pinfunction "DAT0_7") (pintype "passive"))
      (node (ref "U6") (pin "3") (pinfunction "3_3") (pintype "passive"))
    )
    (net (code "48") (name "Net-(P6-Detect)") (class "Default")
      (node (ref "P6") (pin "10") (pinfunction "Detect_10") (pintype "passive"))
      (node (ref "R27") (pin "2") (pinfunction "2_2") (pintype "passive"))
      (node (ref "R29") (pin "1") (pinfunction "1_1") (pintype "passive"))
    )
    (net (code "49") (name "Net-(P6-Protect)") (class "Default")
      (node (ref "P6") (pin "11") (pinfunction "Protect_11") (pintype "passive"))
      (node (ref "R23") (pin "2") (pinfunction "2_2") (pintype "passive"))
      (node (ref "R24") (pin "1") (pinfunction "1_1") (pintype "passive"))
    )
    (net (code "50") (name "Net-(U1-BST)") (class "Default")
      (node (ref "C1") (pin "2") (pinfunction "2_2") (pintype "passive"))
      (node (ref "U1") (pin "1") (pinfunction "BST_1") (pintype "passive"))
    )
    (net (code "51") (name "Net-(U1-ON{slash}~{OFF})") (class "Default")
      (node (ref "R1") (pin "2") (pinfunction "2_2") (pintype "passive"))
      (node (ref "R2") (pin "1") (pinfunction "1_1") (pintype "passive"))
      (node (ref "U1") (pin "5") (pinfunction "ON/~{OFF}_5") (pintype "passive"))
    )
    (net (code "52") (name "Net-(U1-VD)") (class "Default")
      (node (ref "C11") (pin "2") (pinfunction "2_2") (pintype "passive"))
      (node (ref "U1") (pin "2") (pinfunction "VD_2") (pintype "passive"))
    )
    (net (code "53") (name "Net-(U3-VDD)") (class "Default")
      (node (ref "R3") (pin "2") (pinfunction "2_2") (pintype "passive"))
      (node (ref "R9") (pin "1") (pinfunction "1_1") (pintype "passive"))
      (node (ref "U3") (pin "2") (pinfunction "VDD_2") (pintype "passive"))
    )
    (net (code "54") (name "Net-(U3-Vout)") (class "Default")
      (node (ref "C17") (pin "1") (pinfunction "1_1") (pintype "passive"))
      (node (ref "R5") (pin "2") (pinfunction "2_2") (pintype "passive"))
      (node (ref "R7") (pin "1") (pinfunction "1_1") (pintype "passive"))
      (node (ref "U3") (pin "1") (pinfunction "Vout_1") (pintype "passive"))
    )
    (net (code "55") (name "Net-(U4-OSC2{slash}CLKO{slash}AN7{slash}CMP3D{slash}CMP4B{slash}PGA1N2{slash}RP34{slash}RB2)") (class "Default")
      (node (ref "C13") (pin "2") (pinfunction "2_2") (pintype "passive"))
      (node (ref "R4") (pin "2") (pinfunction "2_2") (pintype "passive"))
      (node (ref "U4") (pin "33") (pinfunction "OSC2/CLKO/AN7/CMP3D/CMP4B/PGA1N2/RP34/RB2_33") (pintype "passive"))
      (node (ref "Y1") (pin "3") (pinfunction "3_3") (pintype "passive"))
    )
    (net (code "56") (name "Net-(U4-OSCI{slash}CLKI{slash}AN6{slash}CMP3C{slash}CMP4A{slash}ISRC2{slash}RP33{slash}RB1)") (class "Default")
      (node (ref "C12") (pin "2") (pinfunction "2_2") (pintype "passive"))
      (node (ref "R4") (pin "1") (pinfunction "1_1") (pintype "passive"))
      (node (ref "U4") (pin "32") (pinfunction "OSCI/CLKI/AN6/CMP3C/CMP4A/ISRC2/RP33/RB1_32") (pintype "passive"))
      (node (ref "Y1") (pin "1") (pinfunction "1_1") (pintype "passive"))
    )
    (net (code "57") (name "Net-(U4-VCAP)") (class "Default")
      (node (ref "C20") (pin "2") (pinfunction "2_2") (pintype "passive"))
      (node (ref "U4") (pin "7") (pinfunction "VCAP_7") (pintype "passive"))
    )
    (net (code "58") (name "Net-(U7-CANH)") (class "Default")
      (node (ref "C27") (pin "2") (pinfunction "2_2") (pintype "passive"))
      (node (ref "L3") (pin "3") (pinfunction "3_3") (pintype "passive"))
      (node (ref "R20") (pin "1") (pinfunction "1_1") (pintype "passive"))
      (node (ref "U7") (pin "7") (pinfunction "CANH_7") (pintype "passive"))
    )
    (net (code "59") (name "Net-(U7-CANL)") (class "Default")
      (node (ref "C30") (pin "1") (pinfunction "1_1") (pintype "passive"))
      (node (ref "L3") (pin "2") (pinfunction "2_2") (pintype "passive"))
      (node (ref "R28") (pin "2") (pinfunction "2_2") (pintype "passive"))
      (node (ref "U7") (pin "6") (pinfunction "CANL_6") (pintype "passive"))
    )
    (net (code "60") (name "Net-(U7-RXD)") (class "Default")
      (node (ref "R25") (pin "1") (pinfunction "1_1") (pintype "passive"))
      (node (ref "U7") (pin "4") (pinfunction "RXD_4") (pintype "passive"))
    )
    (net (code "61") (name "Net-(U7-TXD)") (class "Default")
      (node (ref "R21") (pin "1") (pinfunction "1_1") (pintype "passive"))
      (node (ref "U7") (pin "1") (pinfunction "TXD_1") (pintype "passive"))
    )
    (net (code "62") (name "Net-(U8-RX)") (class "Default")
      (node (ref "R22") (pin "2") (pinfunction "2_2") (pintype "passive"))
      (node (ref "U8") (pin "2") (pinfunction "RX_2") (pintype "passive"))
    )
    (net (code "63") (name "Net-(U8-TX)") (class "Default")
      (node (ref "R26") (pin "2") (pinfunction "2_2") (pintype "passive"))
      (node (ref "U8") (pin "3") (pinfunction "TX_3") (pintype "passive"))
    )
    (net (code "64") (name "Vin") (class "Default")
      (node (ref "C2") (pin "1") (pinfunction "1_1") (pintype "passive"))
      (node (ref "C3") (pin "2") (pinfunction "2_2") (pintype "passive"))
      (node (ref "C4") (pin "2") (pinfunction "2_2") (pintype "passive"))
      (node (ref "D1") (pin "1") (pinfunction "K_1") (pintype "passive"))
      (node (ref "F1") (pin "2") (pinfunction "2_2") (pintype "passive"))
      (node (ref "R1") (pin "1") (pinfunction "1_1") (pintype "passive"))
      (node (ref "R3") (pin "1") (pinfunction "1_1") (pintype "passive"))
      (node (ref "U1") (pin "7") (pinfunction "VIN_7") (pintype "passive"))
    )
    (net (code "65") (name "unconnected-(P2-Pad6)") (class "Default")
      (node (ref "P2") (pin "6") (pinfunction "6_6") (pintype "passive"))
    )
    (net (code "66") (name "unconnected-(P6-DAT1-Pad8)") (class "Default")
      (node (ref "P6") (pin "8") (pinfunction "DAT1_8") (pintype "passive"))
    )
    (net (code "67") (name "unconnected-(P6-DAT2-Pad9)") (class "Default")
      (node (ref "P6") (pin "9") (pinfunction "DAT2_9") (pintype "passive"))
    )
    (net (code "68") (name "unconnected-(U4-AN0ALT{slash}RP53{slash}RC5-Pad3)") (class "Default")
      (node (ref "U4") (pin "3") (pinfunction "AN0ALT/RP53/RC5_3") (pintype "passive"))
    )
    (net (code "69") (name "unconnected-(U4-AN1ALT{slash}RP52{slash}RC4-Pad2)") (class "Default")
      (node (ref "U4") (pin "2") (pinfunction "AN1ALT/RP52/RC4_2") (pintype "passive"))
    )
    (net (code "70") (name "unconnected-(U4-AN11{slash}PGA1N3{slash}RP57{slash}RC9-Pad27)") (class "Default")
      (node (ref "U4") (pin "27") (pinfunction "AN11/PGA1N3/RP57/RC9_27") (pintype "passive"))
    )
    (net (code "71") (name "unconnected-(U4-AN14{slash}PGA2N3{slash}RP60{slash}RC12-Pad20)") (class "Default")
      (node (ref "U4") (pin "20") (pinfunction "AN14/PGA2N3/RP60/RC12_20") (pintype "passive"))
    )
    (net (code "72") (name "unconnected-(U4-AN17{slash}RP54{slash}RC6-Pad4)") (class "Default")
      (node (ref "U4") (pin "4") (pinfunction "AN17/RP54/RC6_4") (pintype "passive"))
    )
    (net (code "73") (name "unconnected-(U4-ASCL1{slash}RP56{slash}RC8-Pad38)") (class "Default")
      (node (ref "U4") (pin "38") (pinfunction "ASCL1/RP56/RC8_38") (pintype "passive"))
    )
    (net (code "74") (name "unconnected-(U4-FLT11{slash}RP61{slash}RC13-Pad15)") (class "Default")
      (node (ref "U4") (pin "15") (pinfunction "FLT11/RP61/RC13_15") (pintype "passive"))
    )
    (net (code "75") (name "unconnected-(U4-FLT12{slash}RP48{slash}RC0-Pad14)") (class "Default")
      (node (ref "U4") (pin "14") (pinfunction "FLT12/RP48/RC0_14") (pintype "passive"))
    )
    (net (code "76") (name "unconnected-(U4-PGEC3{slash}SCL2{slash}RP47{slash}RB15-Pad42)") (class "Default")
      (node (ref "U4") (pin "42") (pinfunction "PGEC3/SCL2/RP47/RB15_42") (pintype "passive"))
    )
    (net (code "77") (name "unconnected-(U4-PGED3{slash}SDA2{slash}FLT31{slash}RP40{slash}RB8-Pad41)") (class "Default")
      (node (ref "U4") (pin "41") (pinfunction "PGED3/SDA2/FLT31/RP40/RB8_41") (pintype "passive"))
    )
    (net (code "78") (name "unconnected-(U4-RP51{slash}RC3-Pad5)") (class "Default")
      (node (ref "U4") (pin "5") (pinfunction "RP51/RC3_5") (pintype "passive"))
    )
    (net (code "79") (name "unconnected-(U4-TDO{slash}AN19{slash}PGA2N2{slash}RP37{slash}RB5-Pad43)") (class "Default")
      (node (ref "U4") (pin "43") (pinfunction "TDO/AN19/PGA2N2/RP37/RB5_43") (pintype "passive"))
    )
    (net (code "80") (name "unconnected-(U4-TMS{slash}PWM3H{slash}RP43{slash}RB11-Pad8)") (class "Default")
      (node (ref "U4") (pin "8") (pinfunction "TMS/PWM3H/RP43/RB11_8") (pintype "passive"))
    )
  )
)
